# Esp32_Shield_V3_no_LED.net
KiCad netlist of a schematic drawn in EAGLE
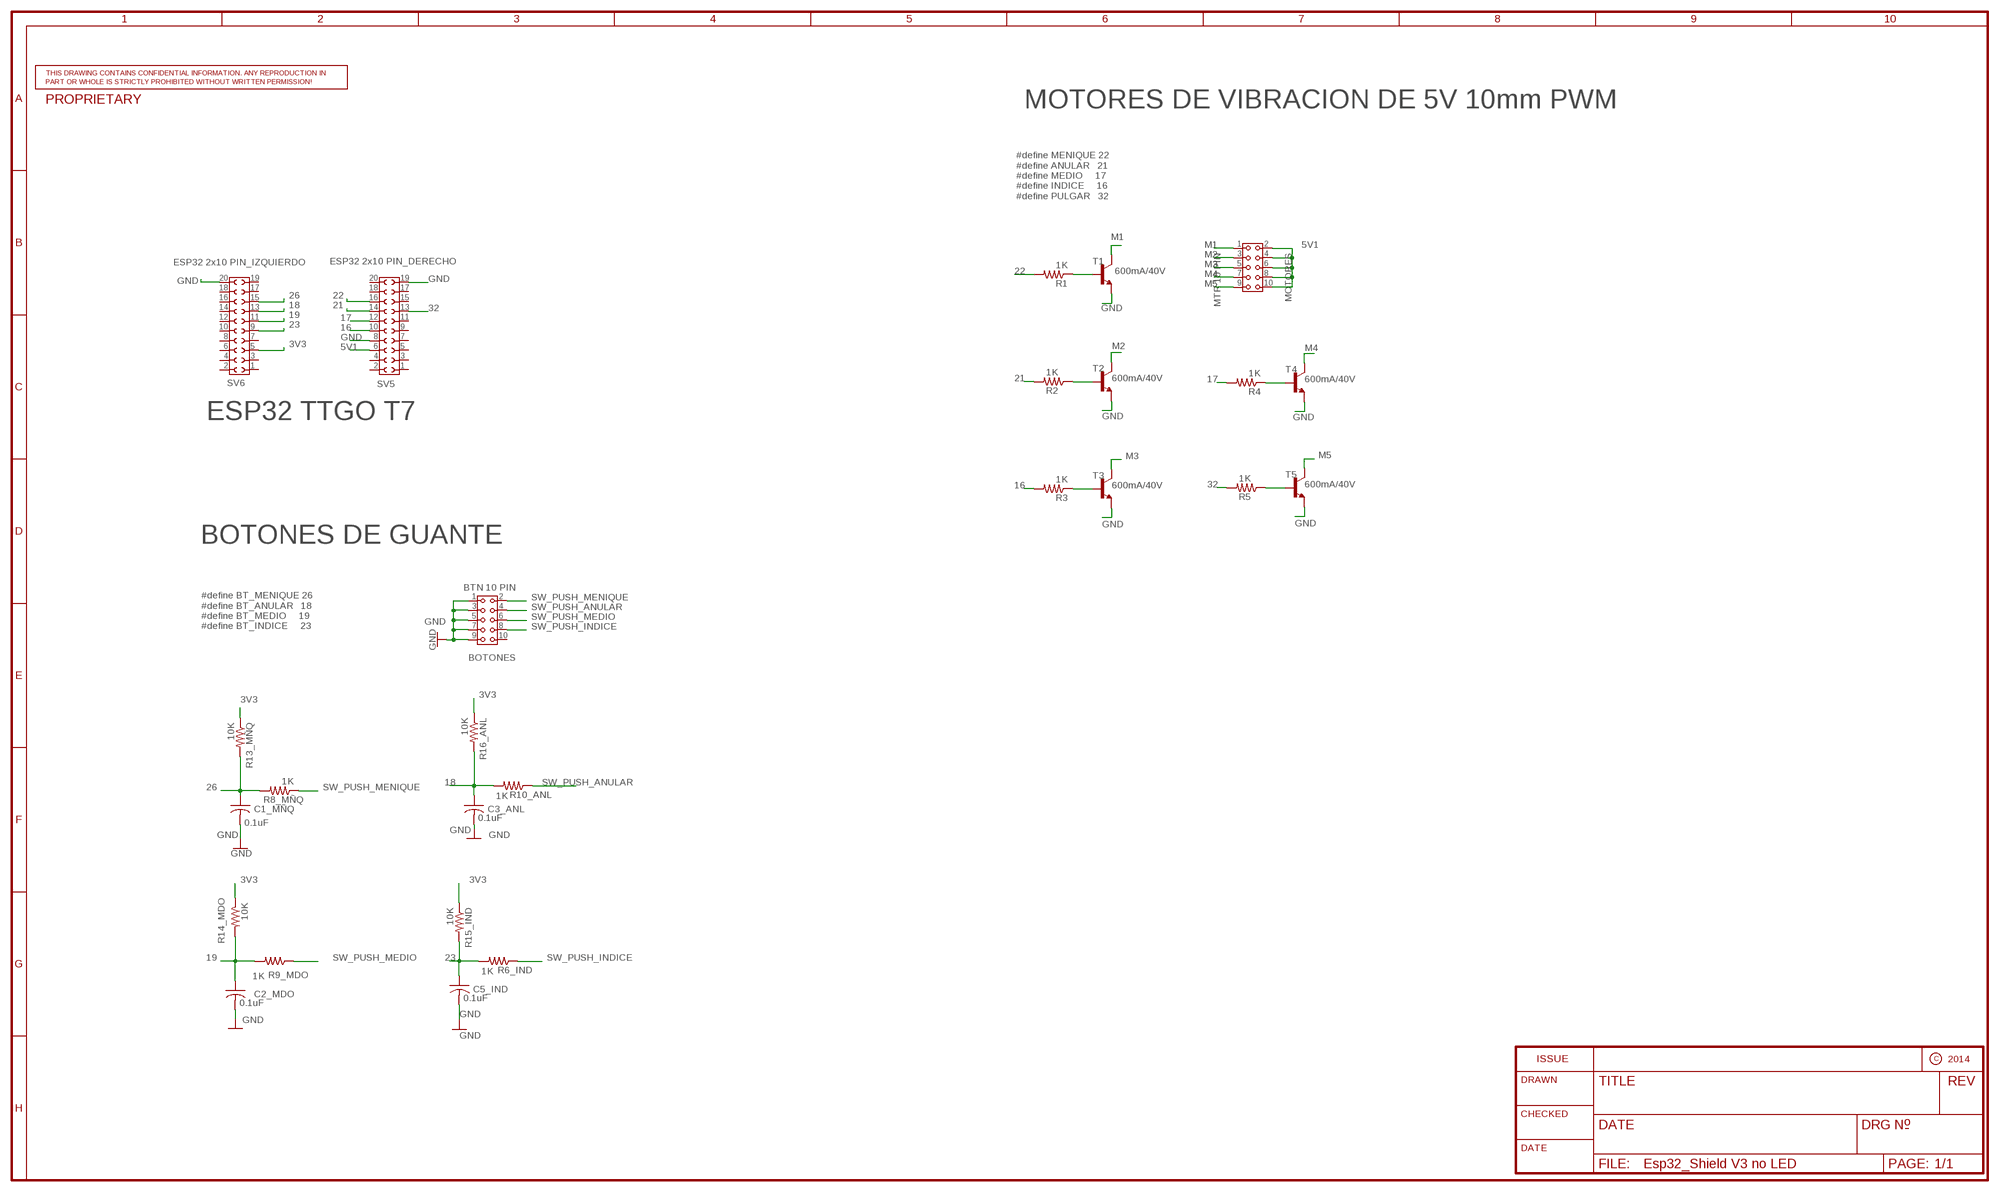
[diagram p0: schematic, sheet 1]

(export (version "E")
  (design (tool "Eeschema 10.0.6"))
  (components
    (comp (ref "BOTONES")
      (value "BTN 10 PIN")
      (footprint "eagle-import:61301021821")
      (libsource (lib "eagle-import") (part "6130XX21821_61301021821"))
    )
    (comp (ref "C1_MÑQ")
      (value "0.1uF")
      (footprint "eagle-import:C0805")
      (libsource (lib "eagle-import") (part "C-USC0805"))
    )
    (comp (ref "C2_MDO")
      (value "0.1uF")
      (footprint "eagle-import:C0805")
      (libsource (lib "eagle-import") (part "C-USC0805"))
    )
    (comp (ref "C3_ANL")
      (value "0.1uF")
      (footprint "eagle-import:C0805")
      (libsource (lib "eagle-import") (part "C-USC0805"))
    )
    (comp (ref "C5_IND")
      (value "0.1uF")
      (footprint "eagle-import:C0805")
      (libsource (lib "eagle-import") (part "C-USC0805"))
    )
    (comp (ref "MOTORES")
      (value "MTR 10 PIN")
      (footprint "eagle-import:61301021821")
      (libsource (lib "eagle-import") (part "6130XX21821_61301021821"))
    )
    (comp (ref "R1")
      (value "1K")
      (footprint "eagle-import:R0805")
      (libsource (lib "eagle-import") (part "R-US_R0805"))
    )
    (comp (ref "R2")
      (value "1K")
      (footprint "eagle-import:R0805")
      (libsource (lib "eagle-import") (part "R-US_R0805"))
    )
    (comp (ref "R3")
      (value "1K")
      (footprint "eagle-import:R0805")
      (libsource (lib "eagle-import") (part "R-US_R0805"))
    )
    (comp (ref "R4")
      (value "1K")
      (footprint "eagle-import:R0805")
      (libsource (lib "eagle-import") (part "R-US_R0805"))
    )
    (comp (ref "R5")
      (value "1K")
      (footprint "eagle-import:R0805")
      (libsource (lib "eagle-import") (part "R-US_R0805"))
    )
    (comp (ref "R6_IND")
      (value "1K")
      (footprint "eagle-import:R0805")
      (libsource (lib "eagle-import") (part "R-US_R0805"))
    )
    (comp (ref "R8_MÑQ")
      (value "1K")
      (footprint "eagle-import:R0805")
      (libsource (lib "eagle-import") (part "R-US_R0805"))
    )
    (comp (ref "R9_MDO")
      (value "1K")
      (footprint "eagle-import:R0805")
      (libsource (lib "eagle-import") (part "R-US_R0805"))
    )
    (comp (ref "R10_ANL")
      (value "1K")
      (footprint "eagle-import:R0805")
      (libsource (lib "eagle-import") (part "R-US_R0805"))
    )
    (comp (ref "R13_MÑQ")
      (value "10K")
      (footprint "eagle-import:R0805")
      (libsource (lib "eagle-import") (part "R-US_R0805"))
    )
    (comp (ref "R14_MDO")
      (value "10K")
      (footprint "eagle-import:R0805")
      (libsource (lib "eagle-import") (part "R-US_R0805"))
    )
    (comp (ref "R15_IND")
      (value "10K")
      (footprint "eagle-import:R0805")
      (libsource (lib "eagle-import") (part "R-US_R0805"))
    )
    (comp (ref "R16_ANL")
      (value "10K")
      (footprint "eagle-import:R0805")
      (libsource (lib "eagle-import") (part "R-US_R0805"))
    )
    (comp (ref "SV5")
      (value "ESP32 2x10 PIN_DERECHO")
      (footprint "eagle-import:61302021821")
      (libsource (lib "eagle-import") (part "6130XX21821_61302021821"))
    )
    (comp (ref "SV6")
      (value "ESP32 2x10 PIN_IZQUIERDO")
      (footprint "eagle-import:61302021821")
      (libsource (lib "eagle-import") (part "6130XX21821_61302021821"))
    )
    (comp (ref "T1")
      (value "600mA/40V")
      (footprint "eagle-import:SOT23-3")
      (libsource (lib "eagle-import") (part "TRANS_NPN-MMBT2222AL"))
    )
    (comp (ref "T2")
      (value "600mA/40V")
      (footprint "eagle-import:SOT23-3")
      (libsource (lib "eagle-import") (part "TRANS_NPN-MMBT2222AL"))
    )
    (comp (ref "T3")
      (value "600mA/40V")
      (footprint "eagle-import:SOT23-3")
      (libsource (lib "eagle-import") (part "TRANS_NPN-MMBT2222AL"))
    )
    (comp (ref "T4")
      (value "600mA/40V")
      (footprint "eagle-import:SOT23-3")
      (libsource (lib "eagle-import") (part "TRANS_NPN-MMBT2222AL"))
    )
    (comp (ref "T5")
      (value "600mA/40V")
      (footprint "eagle-import:SOT23-3")
      (libsource (lib "eagle-import") (part "TRANS_NPN-MMBT2222AL"))
    )
  )
  (nets
    (net (code "1") (name "/3V3") (class "Default")
      (node (ref "R13_MÑQ") (pin "1") (pinfunction "1_1") (pintype "passive"))
      (node (ref "R14_MDO") (pin "1") (pinfunction "1_1") (pintype "passive"))
      (node (ref "R15_IND") (pin "1") (pinfunction "1_1") (pintype "passive"))
      (node (ref "R16_ANL") (pin "1") (pinfunction "1_1") (pintype "passive"))
      (node (ref "SV6") (pin "5") (pinfunction "5_5") (pintype "passive"))
    )
    (net (code "2") (name "/5V1") (class "Default")
      (node (ref "MOTORES") (pin "10") (pinfunction "10_10") (pintype "passive"))
      (node (ref "MOTORES") (pin "2") (pinfunction "2_2") (pintype "passive"))
      (node (ref "MOTORES") (pin "4") (pinfunction "4_4") (pintype "passive"))
      (node (ref "MOTORES") (pin "6") (pinfunction "6_6") (pintype "passive"))
      (node (ref "MOTORES") (pin "8") (pinfunction "8_8") (pintype "passive"))
      (node (ref "SV5") (pin "6") (pinfunction "6_6") (pintype "passive"))
    )
    (net (code "3") (name "/16") (class "Default")
      (node (ref "R3") (pin "2") (pinfunction "2_2") (pintype "passive"))
      (node (ref "SV5") (pin "10") (pinfunction "10_10") (pintype "passive"))
    )
    (net (code "4") (name "/17") (class "Default")
      (node (ref "R4") (pin "2") (pinfunction "2_2") (pintype "passive"))
      (node (ref "SV5") (pin "12") (pinfunction "12_12") (pintype "passive"))
    )
    (net (code "5") (name "/18") (class "Default")
      (node (ref "C3_ANL") (pin "1") (pinfunction "1_1") (pintype "passive"))
      (node (ref "R10_ANL") (pin "2") (pinfunction "2_2") (pintype "passive"))
      (node (ref "R16_ANL") (pin "2") (pinfunction "2_2") (pintype "passive"))
      (node (ref "SV6") (pin "13") (pinfunction "13_13") (pintype "passive"))
    )
    (net (code "6") (name "/19") (class "Default")
      (node (ref "C2_MDO") (pin "1") (pinfunction "1_1") (pintype "passive"))
      (node (ref "R14_MDO") (pin "2") (pinfunction "2_2") (pintype "passive"))
      (node (ref "R9_MDO") (pin "2") (pinfunction "2_2") (pintype "passive"))
      (node (ref "SV6") (pin "11") (pinfunction "11_11") (pintype "passive"))
    )
    (net (code "7") (name "/21") (class "Default")
      (node (ref "R2") (pin "2") (pinfunction "2_2") (pintype "passive"))
      (node (ref "SV5") (pin "14") (pinfunction "14_14") (pintype "passive"))
    )
    (net (code "8") (name "/22") (class "Default")
      (node (ref "R1") (pin "2") (pinfunction "2_2") (pintype "passive"))
      (node (ref "SV5") (pin "16") (pinfunction "16_16") (pintype "passive"))
    )
    (net (code "9") (name "/23") (class "Default")
      (node (ref "C5_IND") (pin "1") (pinfunction "1_1") (pintype "passive"))
      (node (ref "R15_IND") (pin "2") (pinfunction "2_2") (pintype "passive"))
      (node (ref "R6_IND") (pin "2") (pinfunction "2_2") (pintype "passive"))
      (node (ref "SV6") (pin "9") (pinfunction "9_9") (pintype "passive"))
    )
    (net (code "10") (name "/26") (class "Default")
      (node (ref "C1_MÑQ") (pin "1") (pinfunction "1_1") (pintype "passive"))
      (node (ref "R13_MÑQ") (pin "2") (pinfunction "2_2") (pintype "passive"))
      (node (ref "R8_MÑQ") (pin "2") (pinfunction "2_2") (pintype "passive"))
      (node (ref "SV6") (pin "15") (pinfunction "15_15") (pintype "passive"))
    )
    (net (code "11") (name "/32") (class "Default")
      (node (ref "R5") (pin "2") (pinfunction "2_2") (pintype "passive"))
      (node (ref "SV5") (pin "13") (pinfunction "13_13") (pintype "passive"))
    )
    (net (code "12") (name "/M1") (class "Default")
      (node (ref "MOTORES") (pin "1") (pinfunction "1_1") (pintype "passive"))
      (node (ref "T1") (pin "3") (pinfunction "C_3") (pintype "passive"))
    )
    (net (code "13") (name "/M2") (class "Default")
      (node (ref "MOTORES") (pin "3") (pinfunction "3_3") (pintype "passive"))
      (node (ref "T2") (pin "3") (pinfunction "C_3") (pintype "passive"))
    )
    (net (code "14") (name "/M3") (class "Default")
      (node (ref "MOTORES") (pin "5") (pinfunction "5_5") (pintype "passive"))
      (node (ref "T3") (pin "3") (pinfunction "C_3") (pintype "passive"))
    )
    (net (code "15") (name "/M4") (class "Default")
      (node (ref "MOTORES") (pin "7") (pinfunction "7_7") (pintype "passive"))
      (node (ref "T4") (pin "3") (pinfunction "C_3") (pintype "passive"))
    )
    (net (code "16") (name "/M5") (class "Default")
      (node (ref "MOTORES") (pin "9") (pinfunction "9_9") (pintype "passive"))
      (node (ref "T5") (pin "3") (pinfunction "C_3") (pintype "passive"))
    )
    (net (code "17") (name "/SW_PUSH_ANULAR") (class "Default")
      (node (ref "BOTONES") (pin "4") (pinfunction "4_4") (pintype "passive"))
      (node (ref "R10_ANL") (pin "1") (pinfunction "1_1") (pintype "passive"))
    )
    (net (code "18") (name "/SW_PUSH_INDICE") (class "Default")
      (node (ref "BOTONES") (pin "8") (pinfunction "8_8") (pintype "passive"))
      (node (ref "R6_IND") (pin "1") (pinfunction "1_1") (pintype "passive"))
    )
    (net (code "19") (name "/SW_PUSH_MEDIO") (class "Default")
      (node (ref "BOTONES") (pin "6") (pinfunction "6_6") (pintype "passive"))
      (node (ref "R9_MDO") (pin "1") (pinfunction "1_1") (pintype "passive"))
    )
    (net (code "20") (name "/SW_PUSH_MENIQUE") (class "Default")
      (node (ref "BOTONES") (pin "2") (pinfunction "2_2") (pintype "passive"))
      (node (ref "R8_MÑQ") (pin "1") (pinfunction "1_1") (pintype "passive"))
    )
    (net (code "21") (name "GND") (class "Default")
      (node (ref "BOTONES") (pin "1") (pinfunction "1_1") (pintype "passive"))
      (node (ref "BOTONES") (pin "3") (pinfunction "3_3") (pintype "passive"))
      (node (ref "BOTONES") (pin "5") (pinfunction "5_5") (pintype "passive"))
      (node (ref "BOTONES") (pin "7") (pinfunction "7_7") (pintype "passive"))
      (node (ref "BOTONES") (pin "9") (pinfunction "9_9") (pintype "passive"))
      (node (ref "C1_MÑQ") (pin "2") (pinfunction "2_2") (pintype "passive"))
      (node (ref "C2_MDO") (pin "2") (pinfunction "2_2") (pintype "passive"))
      (node (ref "C3_ANL") (pin "2") (pinfunction "2_2") (pintype "passive"))
      (node (ref "C5_IND") (pin "2") (pinfunction "2_2") (pintype "passive"))
      (node (ref "SV5") (pin "19") (pinfunction "19_19") (pintype "passive"))
      (node (ref "SV5") (pin "8") (pinfunction "8_8") (pintype "passive"))
      (node (ref "SV6") (pin "20") (pinfunction "20_20") (pintype "passive"))
      (node (ref "T1") (pin "2") (pinfunction "E_2") (pintype "passive"))
      (node (ref "T2") (pin "2") (pinfunction "E_2") (pintype "passive"))
      (node (ref "T3") (pin "2") (pinfunction "E_2") (pintype "passive"))
      (node (ref "T4") (pin "2") (pinfunction "E_2") (pintype "passive"))
      (node (ref "T5") (pin "2") (pinfunction "E_2") (pintype "passive"))
    )
    (net (code "22") (name "Net-(T1-B)") (class "Default")
      (node (ref "R1") (pin "1") (pinfunction "1_1") (pintype "passive"))
      (node (ref "T1") (pin "1") (pinfunction "B_1") (pintype "passive"))
    )
    (net (code "23") (name "Net-(T2-B)") (class "Default")
      (node (ref "R2") (pin "1") (pinfunction "1_1") (pintype "passive"))
      (node (ref "T2") (pin "1") (pinfunction "B_1") (pintype "passive"))
    )
    (net (code "24") (name "Net-(T3-B)") (class "Default")
      (node (ref "R3") (pin "1") (pinfunction "1_1") (pintype "passive"))
      (node (ref "T3") (pin "1") (pinfunction "B_1") (pintype "passive"))
    )
    (net (code "25") (name "Net-(T4-B)") (class "Default")
      (node (ref "R4") (pin "1") (pinfunction "1_1") (pintype "passive"))
      (node (ref "T4") (pin "1") (pinfunction "B_1") (pintype "passive"))
    )
    (net (code "26") (name "Net-(T5-B)") (class "Default")
      (node (ref "R5") (pin "1") (pinfunction "1_1") (pintype "passive"))
      (node (ref "T5") (pin "1") (pinfunction "B_1") (pintype "passive"))
    )
    (net (code "27") (name "unconnected-(BOTONES-Pad10)") (class "Default")
      (node (ref "BOTONES") (pin "10") (pinfunction "10_10") (pintype "passive"))
    )
    (net (code "28") (name "unconnected-(SV5-Pad1)") (class "Default")
      (node (ref "SV5") (pin "1") (pinfunction "1_1") (pintype "passive"))
    )
    (net (code "29") (name "unconnected-(SV5-Pad2)") (class "Default")
      (node (ref "SV5") (pin "2") (pinfunction "2_2") (pintype "passive"))
    )
    (net (code "30") (name "unconnected-(SV5-Pad3)") (class "Default")
      (node (ref "SV5") (pin "3") (pinfunction "3_3") (pintype "passive"))
    )
    (net (code "31") (name "unconnected-(SV5-Pad4)") (class "Default")
      (node (ref "SV5") (pin "4") (pinfunction "4_4") (pintype "passive"))
    )
    (net (code "32") (name "unconnected-(SV5-Pad5)") (class "Default")
      (node (ref "SV5") (pin "5") (pinfunction "5_5") (pintype "passive"))
    )
    (net (code "33") (name "unconnected-(SV5-Pad7)") (class "Default")
      (node (ref "SV5") (pin "7") (pinfunction "7_7") (pintype "passive"))
    )
    (net (code "34") (name "unconnected-(SV5-Pad9)") (class "Default")
      (node (ref "SV5") (pin "9") (pinfunction "9_9") (pintype "passive"))
    )
    (net (code "35") (name "unconnected-(SV5-Pad11)") (class "Default")
      (node (ref "SV5") (pin "11") (pinfunction "11_11") (pintype "passive"))
    )
    (net (code "36") (name "unconnected-(SV5-Pad15)") (class "Default")
      (node (ref "SV5") (pin "15") (pinfunction "15_15") (pintype "passive"))
    )
    (net (code "37") (name "unconnected-(SV5-Pad17)") (class "Default")
      (node (ref "SV5") (pin "17") (pinfunction "17_17") (pintype "passive"))
    )
    (net (code "38") (name "unconnected-(SV5-Pad18)") (class "Default")
      (node (ref "SV5") (pin "18") (pinfunction "18_18") (pintype "passive"))
    )
    (net (code "39") (name "unconnected-(SV5-Pad20)") (class "Default")
      (node (ref "SV5") (pin "20") (pinfunction "20_20") (pintype "passive"))
    )
    (net (code "40") (name "unconnected-(SV6-Pad1)") (class "Default")
      (node (ref "SV6") (pin "1") (pinfunction "1_1") (pintype "passive"))
    )
    (net (code "41") (name "unconnected-(SV6-Pad2)") (class "Default")
      (node (ref "SV6") (pin "2") (pinfunction "2_2") (pintype "passive"))
    )
    (net (code "42") (name "unconnected-(SV6-Pad3)") (class "Default")
      (node (ref "SV6") (pin "3") (pinfunction "3_3") (pintype "passive"))
    )
    (net (code "43") (name "unconnected-(SV6-Pad4)") (class "Default")
      (node (ref "SV6") (pin "4") (pinfunction "4_4") (pintype "passive"))
    )
    (net (code "44") (name "unconnected-(SV6-Pad6)") (class "Default")
      (node (ref "SV6") (pin "6") (pinfunction "6_6") (pintype "passive"))
    )
    (net (code "45") (name "unconnected-(SV6-Pad7)") (class "Default")
      (node (ref "SV6") (pin "7") (pinfunction "7_7") (pintype "passive"))
    )
    (net (code "46") (name "unconnected-(SV6-Pad8)") (class "Default")
      (node (ref "SV6") (pin "8") (pinfunction "8_8") (pintype "passive"))
    )
    (net (code "47") (name "unconnected-(SV6-Pad10)") (class "Default")
      (node (ref "SV6") (pin "10") (pinfunction "10_10") (pintype "passive"))
    )
    (net (code "48") (name "unconnected-(SV6-Pad12)") (class "Default")
      (node (ref "SV6") (pin "12") (pinfunction "12_12") (pintype "passive"))
    )
    (net (code "49") (name "unconnected-(SV6-Pad14)") (class "Default")
      (node (ref "SV6") (pin "14") (pinfunction "14_14") (pintype "passive"))
    )
    (net (code "50") (name "unconnected-(SV6-Pad16)") (class "Default")
      (node (ref "SV6") (pin "16") (pinfunction "16_16") (pintype "passive"))
    )
    (net (code "51") (name "unconnected-(SV6-Pad17)") (class "Default")
      (node (ref "SV6") (pin "17") (pinfunction "17_17") (pintype "passive"))
    )
    (net (code "52") (name "unconnected-(SV6-Pad18)") (class "Default")
      (node (ref "SV6") (pin "18") (pinfunction "18_18") (pintype "passive"))
    )
    (net (code "53") (name "unconnected-(SV6-Pad19)") (class "Default")
      (node (ref "SV6") (pin "19") (pinfunction "19_19") (pintype "passive"))
    )
  )
)
